# TA_590_mock_sch.net
KiCad netlist of a schematic drawn in EAGLE
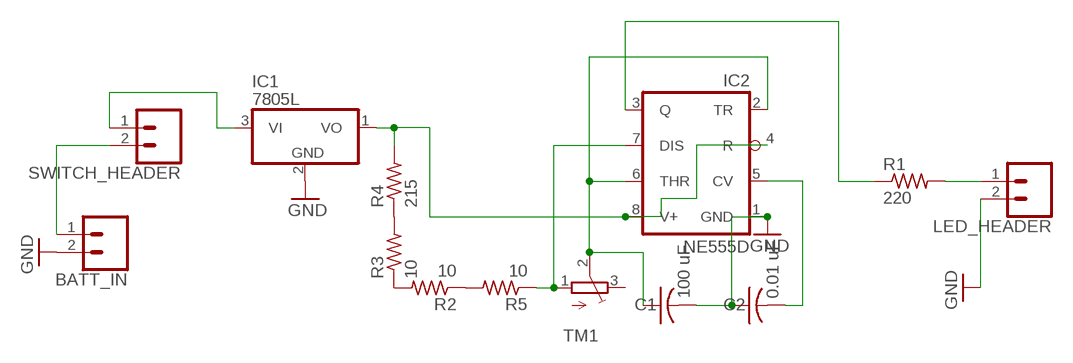
[diagram p0: schematic, sheet 1]

(export (version "E")
  (design (tool "Eeschema 10.0.6"))
  (components
    (comp (ref "BATT_IN")
      (value "CONN_02")
      (footprint "eagle-import:1X02")
      (libsource (lib "eagle-import") (part "CONN_02"))
    )
    (comp (ref "C1")
      (value "100 uF")
      (footprint "eagle-import:C0805")
      (libsource (lib "eagle-import") (part "C-USC0805"))
    )
    (comp (ref "C2")
      (value "0.01 uF")
      (footprint "eagle-import:C0805")
      (libsource (lib "eagle-import") (part "C-USC0805"))
    )
    (comp (ref "IC1")
      (value "7805L")
      (footprint "eagle-import:TO92")
      (libsource (lib "eagle-import") (part "78L05"))
    )
    (comp (ref "IC2")
      (value "NE555D")
      (footprint "eagle-import:SO08")
      (libsource (lib "eagle-import") (part "555DNE"))
    )
    (comp (ref "LED_HEADER")
      (value "CONN_02")
      (footprint "eagle-import:1X02")
      (libsource (lib "eagle-import") (part "CONN_02"))
    )
    (comp (ref "R1")
      (value "220")
      (footprint "eagle-import:R0805")
      (libsource (lib "eagle-import") (part "R-US_R0805"))
    )
    (comp (ref "R2")
      (value "10")
      (footprint "eagle-import:R0805")
      (libsource (lib "eagle-import") (part "R-US_R0805"))
    )
    (comp (ref "R3")
      (value "10")
      (footprint "eagle-import:R0805")
      (libsource (lib "eagle-import") (part "R-US_R0805"))
    )
    (comp (ref "R4")
      (value "215")
      (footprint "eagle-import:R0805")
      (libsource (lib "eagle-import") (part "R-US_R0805"))
    )
    (comp (ref "R5")
      (value "10")
      (footprint "eagle-import:R0805")
      (libsource (lib "eagle-import") (part "R-US_R0805"))
    )
    (comp (ref "SWITCH_HEADER")
      (value "CONN_02")
      (footprint "eagle-import:1X02")
      (libsource (lib "eagle-import") (part "CONN_02"))
    )
    (comp (ref "TM1")
      (value "TRIMPOTTC33X")
      (footprint "eagle-import:TC33X")
      (libsource (lib "eagle-import") (part "TRIMPOTTC33X"))
    )
  )
  (nets
    (net (code "1") (name "GND") (class "Default")
      (node (ref "BATT_IN") (pin "2") (pinfunction "2_2") (pintype "passive"))
      (node (ref "C1") (pin "2") (pinfunction "2_2") (pintype "passive"))
      (node (ref "C2") (pin "1") (pinfunction "1_1") (pintype "passive"))
      (node (ref "IC1") (pin "2") (pinfunction "GND_2") (pintype "passive"))
      (node (ref "IC2") (pin "1") (pinfunction "GND_1") (pintype "power_in"))
      (node (ref "LED_HEADER") (pin "2") (pinfunction "2_2") (pintype "passive"))
    )
    (net (code "2") (name "Net-(BATT_IN-Pad1)") (class "Default")
      (node (ref "BATT_IN") (pin "1") (pinfunction "1_1") (pintype "passive"))
      (node (ref "SWITCH_HEADER") (pin "2") (pinfunction "2_2") (pintype "passive"))
    )
    (net (code "3") (name "Net-(IC1-VI)") (class "Default")
      (node (ref "IC1") (pin "3") (pinfunction "VI_3") (pintype "input"))
      (node (ref "SWITCH_HEADER") (pin "1") (pinfunction "1_1") (pintype "passive"))
    )
    (net (code "4") (name "Net-(IC1-VO)") (class "Default")
      (node (ref "IC1") (pin "1") (pinfunction "VO_1") (pintype "passive"))
      (node (ref "IC2") (pin "4") (pinfunction "R_4") (pintype "input"))
      (node (ref "IC2") (pin "8") (pinfunction "V+_8") (pintype "power_in"))
      (node (ref "R4") (pin "2") (pinfunction "2_2") (pintype "passive"))
    )
    (net (code "5") (name "Net-(IC2-CV)") (class "Default")
      (node (ref "C2") (pin "2") (pinfunction "2_2") (pintype "passive"))
      (node (ref "IC2") (pin "5") (pinfunction "CV_5") (pintype "input"))
    )
    (net (code "6") (name "Net-(IC2-DIS)") (class "Default")
      (node (ref "IC2") (pin "7") (pinfunction "DIS_7") (pintype "input"))
      (node (ref "R5") (pin "1") (pinfunction "1_1") (pintype "passive"))
      (node (ref "TM1") (pin "1") (pinfunction "A_1") (pintype "passive"))
    )
    (net (code "7") (name "Net-(IC2-Q)") (class "Default")
      (node (ref "IC2") (pin "3") (pinfunction "Q_3") (pintype "output"))
      (node (ref "R1") (pin "1") (pinfunction "1_1") (pintype "passive"))
    )
    (net (code "8") (name "Net-(IC2-THR)") (class "Default")
      (node (ref "C1") (pin "1") (pinfunction "1_1") (pintype "passive"))
      (node (ref "IC2") (pin "2") (pinfunction "TR_2") (pintype "input"))
      (node (ref "IC2") (pin "6") (pinfunction "THR_6") (pintype "input"))
      (node (ref "TM1") (pin "2") (pinfunction "S_2") (pintype "passive"))
    )
    (net (code "9") (name "Net-(LED_HEADER-Pad1)") (class "Default")
      (node (ref "LED_HEADER") (pin "1") (pinfunction "1_1") (pintype "passive"))
      (node (ref "R1") (pin "2") (pinfunction "2_2") (pintype "passive"))
    )
    (net (code "10") (name "Net-(R2-Pad1)") (class "Default")
      (node (ref "R2") (pin "1") (pinfunction "1_1") (pintype "passive"))
      (node (ref "R5") (pin "2") (pinfunction "2_2") (pintype "passive"))
    )
    (net (code "11") (name "Net-(R2-Pad2)") (class "Default")
      (node (ref "R2") (pin "2") (pinfunction "2_2") (pintype "passive"))
      (node (ref "R3") (pin "1") (pinfunction "1_1") (pintype "passive"))
    )
    (net (code "12") (name "Net-(R3-Pad2)") (class "Default")
      (node (ref "R3") (pin "2") (pinfunction "2_2") (pintype "passive"))
      (node (ref "R4") (pin "1") (pinfunction "1_1") (pintype "passive"))
    )
    (net (code "13") (name "unconnected-(TM1-E-Pad3)") (class "Default")
      (node (ref "TM1") (pin "3") (pinfunction "E_3") (pintype "passive"))
    )
  )
)
